# avr_isp_adapter.net
KiCad netlist of a schematic drawn in EAGLE
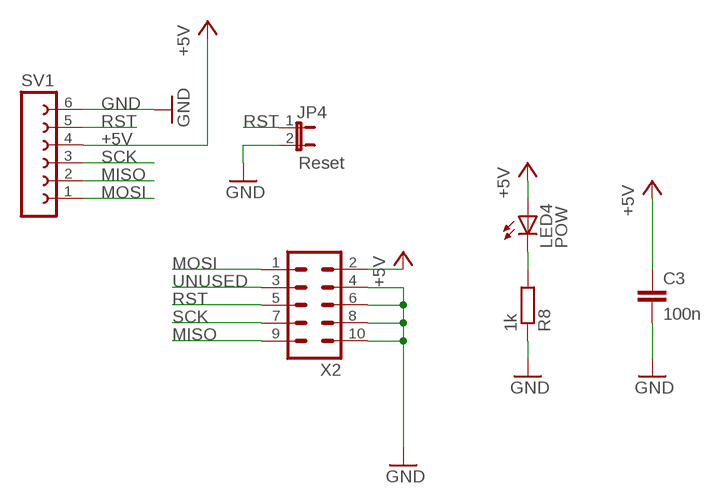
[diagram p0: schematic, sheet 1]

(export (version "E")
  (design (tool "Eeschema 10.0.6"))
  (components
    (comp (ref "C3")
      (value "100n")
      (footprint "eagle-import:C050-025X075")
      (libsource (lib "eagle-import") (part "C-EU050-025X075"))
    )
    (comp (ref "JP4")
      (value "Reset")
      (footprint "eagle-import:JP1")
      (libsource (lib "eagle-import") (part "JP1E"))
    )
    (comp (ref "LED4")
      (value "POW")
      (footprint "eagle-import:LED5MM")
      (libsource (lib "eagle-import") (part "LED5MM"))
    )
    (comp (ref "R8")
      (value "1k")
      (footprint "eagle-import:0204_5")
      (libsource (lib "eagle-import") (part "R-EU_0204/5"))
    )
    (comp (ref "SV1")
      (value "FE06W")
      (footprint "eagle-import:FE06W")
      (libsource (lib "eagle-import") (part "FE06W"))
    )
    (comp (ref "X2")
      (value "ML10L")
      (footprint "eagle-import:ML10L")
      (libsource (lib "eagle-import") (part "ML10L"))
    )
  )
  (nets
    (net (code "1") (name "+5V") (class "Default")
      (node (ref "C3") (pin "1") (pinfunction "1_1") (pintype "passive"))
      (node (ref "LED4") (pin "A") (pinfunction "A_A") (pintype "passive"))
      (node (ref "SV1") (pin "4") (pinfunction "4_4") (pintype "passive"))
      (node (ref "X2") (pin "2") (pinfunction "2_2") (pintype "passive"))
    )
    (net (code "2") (name "/MISO") (class "Default")
      (node (ref "SV1") (pin "2") (pinfunction "2_2") (pintype "passive"))
      (node (ref "X2") (pin "9") (pinfunction "9_9") (pintype "passive"))
    )
    (net (code "3") (name "/MOSI") (class "Default")
      (node (ref "SV1") (pin "1") (pinfunction "1_1") (pintype "passive"))
      (node (ref "X2") (pin "1") (pinfunction "1_1") (pintype "passive"))
    )
    (net (code "4") (name "/RST") (class "Default")
      (node (ref "JP4") (pin "1") (pinfunction "1_1") (pintype "passive"))
      (node (ref "SV1") (pin "5") (pinfunction "5_5") (pintype "passive"))
      (node (ref "X2") (pin "5") (pinfunction "5_5") (pintype "passive"))
    )
    (net (code "5") (name "/SCK") (class "Default")
      (node (ref "SV1") (pin "3") (pinfunction "3_3") (pintype "passive"))
      (node (ref "X2") (pin "7") (pinfunction "7_7") (pintype "passive"))
    )
    (net (code "6") (name "/UNUSED") (class "Default")
      (node (ref "X2") (pin "3") (pinfunction "3_3") (pintype "passive"))
    )
    (net (code "7") (name "GND") (class "Default")
      (node (ref "C3") (pin "2") (pinfunction "2_2") (pintype "passive"))
      (node (ref "JP4") (pin "2") (pinfunction "2_2") (pintype "passive"))
      (node (ref "R8") (pin "1") (pinfunction "1_1") (pintype "passive"))
      (node (ref "SV1") (pin "6") (pinfunction "6_6") (pintype "passive"))
      (node (ref "X2") (pin "10") (pinfunction "10_10") (pintype "passive"))
      (node (ref "X2") (pin "4") (pinfunction "4_4") (pintype "passive"))
      (node (ref "X2") (pin "6") (pinfunction "6_6") (pintype "passive"))
      (node (ref "X2") (pin "8") (pinfunction "8_8") (pintype "passive"))
    )
    (net (code "8") (name "Net-(LED4-C)") (class "Default")
      (node (ref "LED4") (pin "K") (pinfunction "C_K") (pintype "passive"))
      (node (ref "R8") (pin "2") (pinfunction "2_2") (pintype "passive"))
    )
  )
)
